# Line_Follower.net
KiCad netlist of a schematic drawn in EAGLE
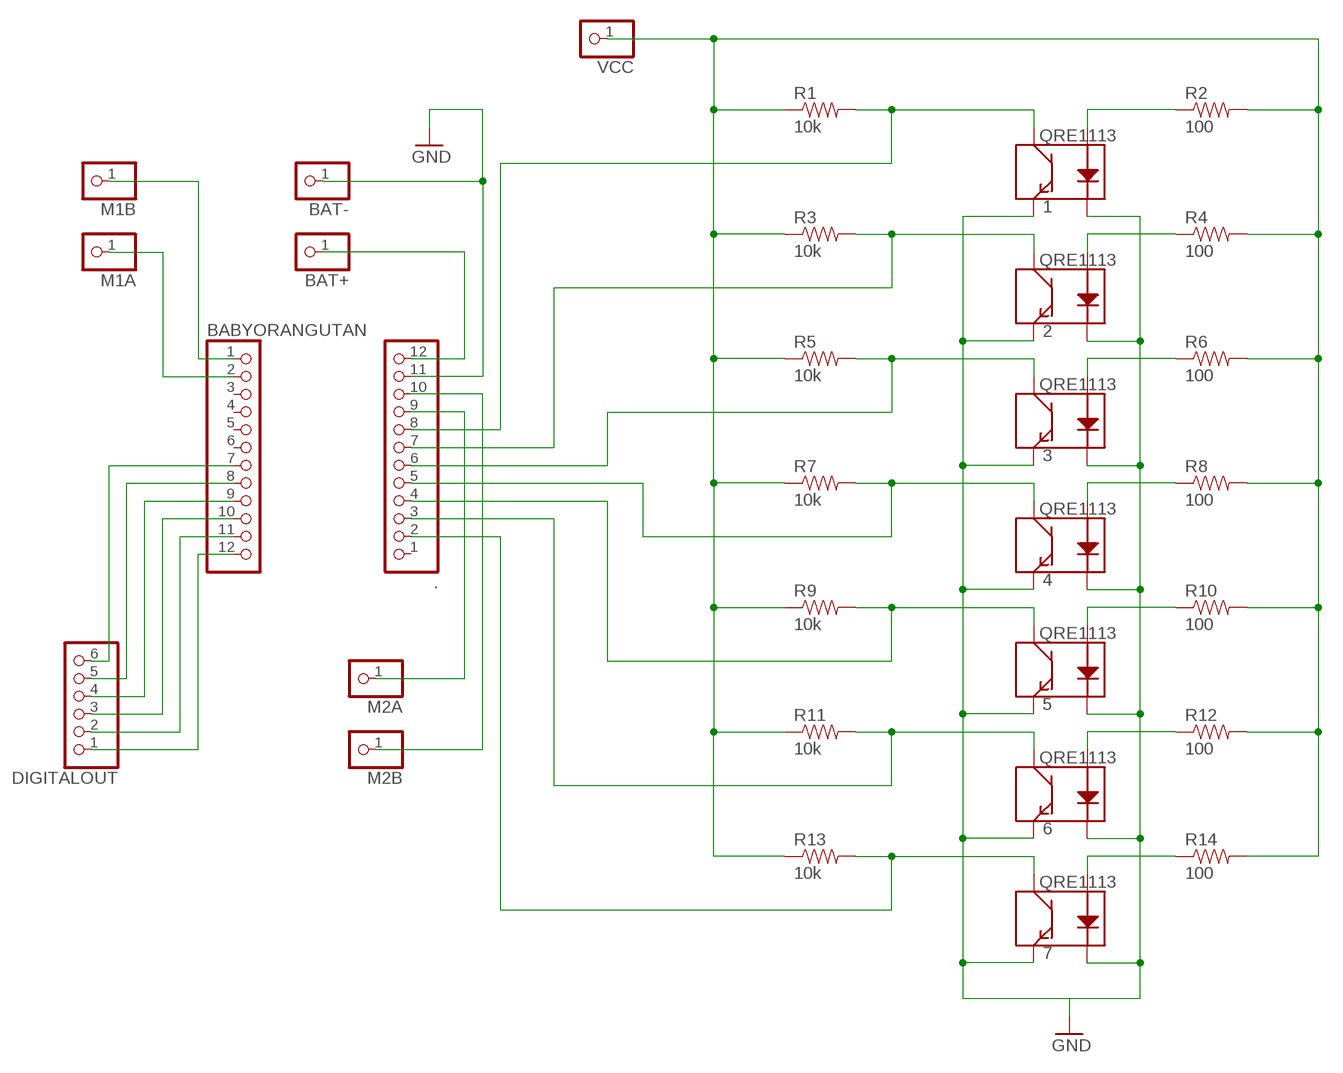
[diagram p0: schematic, sheet 1]

(export (version "E")
  (design (tool "Eeschema 10.0.6"))
  (components
    (comp (ref ".")
      (value "PINHD-1X12")
      (footprint "eagle-import:1X12")
      (libsource (lib "eagle-import") (part "PINHD-1X12"))
    )
    (comp (ref "1")
      (value "QRE1113")
      (footprint "eagle-import:QRE1113")
      (libsource (lib "eagle-import") (part "QRE1113"))
    )
    (comp (ref "2")
      (value "QRE1113")
      (footprint "eagle-import:QRE1113")
      (libsource (lib "eagle-import") (part "QRE1113"))
    )
    (comp (ref "3")
      (value "QRE1113")
      (footprint "eagle-import:QRE1113")
      (libsource (lib "eagle-import") (part "QRE1113"))
    )
    (comp (ref "4")
      (value "QRE1113")
      (footprint "eagle-import:QRE1113")
      (libsource (lib "eagle-import") (part "QRE1113"))
    )
    (comp (ref "5")
      (value "QRE1113")
      (footprint "eagle-import:QRE1113")
      (libsource (lib "eagle-import") (part "QRE1113"))
    )
    (comp (ref "6")
      (value "QRE1113")
      (footprint "eagle-import:QRE1113")
      (libsource (lib "eagle-import") (part "QRE1113"))
    )
    (comp (ref "7")
      (value "QRE1113")
      (footprint "eagle-import:QRE1113")
      (libsource (lib "eagle-import") (part "QRE1113"))
    )
    (comp (ref "BABYORANGUTAN")
      (value "PINHD-1X12")
      (footprint "eagle-import:1X12")
      (libsource (lib "eagle-import") (part "PINHD-1X12"))
    )
    (comp (ref "BAT+")
      (value "PINHD-1X1")
      (footprint "eagle-import:1X01")
      (libsource (lib "eagle-import") (part "PINHD-1X1"))
    )
    (comp (ref "BAT-")
      (value "PINHD-1X1")
      (footprint "eagle-import:1X01")
      (libsource (lib "eagle-import") (part "PINHD-1X1"))
    )
    (comp (ref "DIGITALOUT")
      (value "PINHD-1X6")
      (footprint "eagle-import:1X06")
      (libsource (lib "eagle-import") (part "PINHD-1X6"))
    )
    (comp (ref "M1A")
      (value "PINHD-1X1")
      (footprint "eagle-import:1X01")
      (libsource (lib "eagle-import") (part "PINHD-1X1"))
    )
    (comp (ref "M1B")
      (value "PINHD-1X1")
      (footprint "eagle-import:1X01")
      (libsource (lib "eagle-import") (part "PINHD-1X1"))
    )
    (comp (ref "M2A")
      (value "PINHD-1X1")
      (footprint "eagle-import:1X01")
      (libsource (lib "eagle-import") (part "PINHD-1X1"))
    )
    (comp (ref "M2B")
      (value "PINHD-1X1")
      (footprint "eagle-import:1X01")
      (libsource (lib "eagle-import") (part "PINHD-1X1"))
    )
    (comp (ref "R1")
      (value "10k")
      (footprint "eagle-import:0603-RES")
      (libsource (lib "eagle-import") (part "RESISTOR0603-RES"))
    )
    (comp (ref "R2")
      (value "100")
      (footprint "eagle-import:0805")
      (libsource (lib "eagle-import") (part "RESISTOR0805-RES"))
    )
    (comp (ref "R3")
      (value "10k")
      (footprint "eagle-import:0603-RES")
      (libsource (lib "eagle-import") (part "RESISTOR0603-RES"))
    )
    (comp (ref "R4")
      (value "100")
      (footprint "eagle-import:0805")
      (libsource (lib "eagle-import") (part "RESISTOR0805-RES"))
    )
    (comp (ref "R5")
      (value "10k")
      (footprint "eagle-import:0603-RES")
      (libsource (lib "eagle-import") (part "RESISTOR0603-RES"))
    )
    (comp (ref "R6")
      (value "100")
      (footprint "eagle-import:0805")
      (libsource (lib "eagle-import") (part "RESISTOR0805-RES"))
    )
    (comp (ref "R7")
      (value "10k")
      (footprint "eagle-import:0603-RES")
      (libsource (lib "eagle-import") (part "RESISTOR0603-RES"))
    )
    (comp (ref "R8")
      (value "100")
      (footprint "eagle-import:0805")
      (libsource (lib "eagle-import") (part "RESISTOR0805-RES"))
    )
    (comp (ref "R9")
      (value "10k")
      (footprint "eagle-import:0603-RES")
      (libsource (lib "eagle-import") (part "RESISTOR0603-RES"))
    )
    (comp (ref "R10")
      (value "100")
      (footprint "eagle-import:0805")
      (libsource (lib "eagle-import") (part "RESISTOR0805-RES"))
    )
    (comp (ref "R11")
      (value "10k")
      (footprint "eagle-import:0603-RES")
      (libsource (lib "eagle-import") (part "RESISTOR0603-RES"))
    )
    (comp (ref "R12")
      (value "100")
      (footprint "eagle-import:0805")
      (libsource (lib "eagle-import") (part "RESISTOR0805-RES"))
    )
    (comp (ref "R13")
      (value "10k")
      (footprint "eagle-import:0603-RES")
      (libsource (lib "eagle-import") (part "RESISTOR0603-RES"))
    )
    (comp (ref "R14")
      (value "100")
      (footprint "eagle-import:0805")
      (libsource (lib "eagle-import") (part "RESISTOR0805-RES"))
    )
    (comp (ref "VCC")
      (value "PINHD-1X1")
      (footprint "eagle-import:1X01")
      (libsource (lib "eagle-import") (part "PINHD-1X1"))
    )
  )
  (nets
    (net (code "1") (name "GND") (class "Default")
      (node (ref ".") (pin "11") (pinfunction "11_11") (pintype "passive"))
      (node (ref "1") (pin "2") (pinfunction "K_2") (pintype "bidirectional"))
      (node (ref "1") (pin "4") (pinfunction "E_4") (pintype "bidirectional"))
      (node (ref "2") (pin "2") (pinfunction "K_2") (pintype "bidirectional"))
      (node (ref "2") (pin "4") (pinfunction "E_4") (pintype "bidirectional"))
      (node (ref "3") (pin "2") (pinfunction "K_2") (pintype "bidirectional"))
      (node (ref "3") (pin "4") (pinfunction "E_4") (pintype "bidirectional"))
      (node (ref "4") (pin "2") (pinfunction "K_2") (pintype "bidirectional"))
      (node (ref "4") (pin "4") (pinfunction "E_4") (pintype "bidirectional"))
      (node (ref "5") (pin "2") (pinfunction "K_2") (pintype "bidirectional"))
      (node (ref "5") (pin "4") (pinfunction "E_4") (pintype "bidirectional"))
      (node (ref "6") (pin "2") (pinfunction "K_2") (pintype "bidirectional"))
      (node (ref "6") (pin "4") (pinfunction "E_4") (pintype "bidirectional"))
      (node (ref "7") (pin "2") (pinfunction "K_2") (pintype "bidirectional"))
      (node (ref "7") (pin "4") (pinfunction "E_4") (pintype "bidirectional"))
      (node (ref "BAT-") (pin "1") (pinfunction "1_1") (pintype "passive"))
    )
    (net (code "2") (name "Net-(.-Pad9)") (class "Default")
      (node (ref ".") (pin "9") (pinfunction "9_9") (pintype "passive"))
      (node (ref "M2A") (pin "1") (pinfunction "1_1") (pintype "passive"))
    )
    (net (code "3") (name "Net-(.-Pad10)") (class "Default")
      (node (ref ".") (pin "10") (pinfunction "10_10") (pintype "passive"))
      (node (ref "M2B") (pin "1") (pinfunction "1_1") (pintype "passive"))
    )
    (net (code "4") (name "Net-(.-Pad12)") (class "Default")
      (node (ref ".") (pin "12") (pinfunction "12_12") (pintype "passive"))
      (node (ref "BAT+") (pin "1") (pinfunction "1_1") (pintype "passive"))
    )
    (net (code "5") (name "Net-(1-A)") (class "Default")
      (node (ref "1") (pin "1") (pinfunction "A_1") (pintype "bidirectional"))
      (node (ref "R2") (pin "1") (pinfunction "1_1") (pintype "passive"))
    )
    (net (code "6") (name "Net-(1-C)") (class "Default")
      (node (ref ".") (pin "8") (pinfunction "8_8") (pintype "passive"))
      (node (ref "1") (pin "3") (pinfunction "C_3") (pintype "bidirectional"))
      (node (ref "R1") (pin "2") (pinfunction "2_2") (pintype "passive"))
    )
    (net (code "7") (name "Net-(2-A)") (class "Default")
      (node (ref "2") (pin "1") (pinfunction "A_1") (pintype "bidirectional"))
      (node (ref "R4") (pin "1") (pinfunction "1_1") (pintype "passive"))
    )
    (net (code "8") (name "Net-(2-C)") (class "Default")
      (node (ref ".") (pin "7") (pinfunction "7_7") (pintype "passive"))
      (node (ref "2") (pin "3") (pinfunction "C_3") (pintype "bidirectional"))
      (node (ref "R3") (pin "2") (pinfunction "2_2") (pintype "passive"))
    )
    (net (code "9") (name "Net-(3-A)") (class "Default")
      (node (ref "3") (pin "1") (pinfunction "A_1") (pintype "bidirectional"))
      (node (ref "R6") (pin "1") (pinfunction "1_1") (pintype "passive"))
    )
    (net (code "10") (name "Net-(3-C)") (class "Default")
      (node (ref ".") (pin "6") (pinfunction "6_6") (pintype "passive"))
      (node (ref "3") (pin "3") (pinfunction "C_3") (pintype "bidirectional"))
      (node (ref "R5") (pin "2") (pinfunction "2_2") (pintype "passive"))
    )
    (net (code "11") (name "Net-(4-A)") (class "Default")
      (node (ref "4") (pin "1") (pinfunction "A_1") (pintype "bidirectional"))
      (node (ref "R8") (pin "1") (pinfunction "1_1") (pintype "passive"))
    )
    (net (code "12") (name "Net-(4-C)") (class "Default")
      (node (ref ".") (pin "5") (pinfunction "5_5") (pintype "passive"))
      (node (ref "4") (pin "3") (pinfunction "C_3") (pintype "bidirectional"))
      (node (ref "R7") (pin "2") (pinfunction "2_2") (pintype "passive"))
    )
    (net (code "13") (name "Net-(5-A)") (class "Default")
      (node (ref "5") (pin "1") (pinfunction "A_1") (pintype "bidirectional"))
      (node (ref "R10") (pin "1") (pinfunction "1_1") (pintype "passive"))
    )
    (net (code "14") (name "Net-(5-C)") (class "Default")
      (node (ref ".") (pin "4") (pinfunction "4_4") (pintype "passive"))
      (node (ref "5") (pin "3") (pinfunction "C_3") (pintype "bidirectional"))
      (node (ref "R9") (pin "2") (pinfunction "2_2") (pintype "passive"))
    )
    (net (code "15") (name "Net-(6-A)") (class "Default")
      (node (ref "6") (pin "1") (pinfunction "A_1") (pintype "bidirectional"))
      (node (ref "R12") (pin "1") (pinfunction "1_1") (pintype "passive"))
    )
    (net (code "16") (name "Net-(6-C)") (class "Default")
      (node (ref ".") (pin "3") (pinfunction "3_3") (pintype "passive"))
      (node (ref "6") (pin "3") (pinfunction "C_3") (pintype "bidirectional"))
      (node (ref "R11") (pin "2") (pinfunction "2_2") (pintype "passive"))
    )
    (net (code "17") (name "Net-(7-A)") (class "Default")
      (node (ref "7") (pin "1") (pinfunction "A_1") (pintype "bidirectional"))
      (node (ref "R14") (pin "1") (pinfunction "1_1") (pintype "passive"))
    )
    (net (code "18") (name "Net-(7-C)") (class "Default")
      (node (ref ".") (pin "2") (pinfunction "2_2") (pintype "passive"))
      (node (ref "7") (pin "3") (pinfunction "C_3") (pintype "bidirectional"))
      (node (ref "R13") (pin "2") (pinfunction "2_2") (pintype "passive"))
    )
    (net (code "19") (name "Net-(BABYORANGUTAN-Pad1)") (class "Default")
      (node (ref "BABYORANGUTAN") (pin "1") (pinfunction "1_1") (pintype "passive"))
      (node (ref "M1B") (pin "1") (pinfunction "1_1") (pintype "passive"))
    )
    (net (code "20") (name "Net-(BABYORANGUTAN-Pad2)") (class "Default")
      (node (ref "BABYORANGUTAN") (pin "2") (pinfunction "2_2") (pintype "passive"))
      (node (ref "M1A") (pin "1") (pinfunction "1_1") (pintype "passive"))
    )
    (net (code "21") (name "Net-(BABYORANGUTAN-Pad7)") (class "Default")
      (node (ref "BABYORANGUTAN") (pin "7") (pinfunction "7_7") (pintype "passive"))
      (node (ref "DIGITALOUT") (pin "6") (pinfunction "6_6") (pintype "passive"))
    )
    (net (code "22") (name "Net-(BABYORANGUTAN-Pad8)") (class "Default")
      (node (ref "BABYORANGUTAN") (pin "8") (pinfunction "8_8") (pintype "passive"))
      (node (ref "DIGITALOUT") (pin "5") (pinfunction "5_5") (pintype "passive"))
    )
    (net (code "23") (name "Net-(BABYORANGUTAN-Pad9)") (class "Default")
      (node (ref "BABYORANGUTAN") (pin "9") (pinfunction "9_9") (pintype "passive"))
      (node (ref "DIGITALOUT") (pin "4") (pinfunction "4_4") (pintype "passive"))
    )
    (net (code "24") (name "Net-(BABYORANGUTAN-Pad10)") (class "Default")
      (node (ref "BABYORANGUTAN") (pin "10") (pinfunction "10_10") (pintype "passive"))
      (node (ref "DIGITALOUT") (pin "3") (pinfunction "3_3") (pintype "passive"))
    )
    (net (code "25") (name "Net-(BABYORANGUTAN-Pad11)") (class "Default")
      (node (ref "BABYORANGUTAN") (pin "11") (pinfunction "11_11") (pintype "passive"))
      (node (ref "DIGITALOUT") (pin "2") (pinfunction "2_2") (pintype "passive"))
    )
    (net (code "26") (name "Net-(BABYORANGUTAN-Pad12)") (class "Default")
      (node (ref "BABYORANGUTAN") (pin "12") (pinfunction "12_12") (pintype "passive"))
      (node (ref "DIGITALOUT") (pin "1") (pinfunction "1_1") (pintype "passive"))
    )
    (net (code "27") (name "Net-(R1-Pad1)") (class "Default")
      (node (ref "R1") (pin "1") (pinfunction "1_1") (pintype "passive"))
      (node (ref "R10") (pin "2") (pinfunction "2_2") (pintype "passive"))
      (node (ref "R11") (pin "1") (pinfunction "1_1") (pintype "passive"))
      (node (ref "R12") (pin "2") (pinfunction "2_2") (pintype "passive"))
      (node (ref "R13") (pin "1") (pinfunction "1_1") (pintype "passive"))
      (node (ref "R14") (pin "2") (pinfunction "2_2") (pintype "passive"))
      (node (ref "R2") (pin "2") (pinfunction "2_2") (pintype "passive"))
      (node (ref "R3") (pin "1") (pinfunction "1_1") (pintype "passive"))
      (node (ref "R4") (pin "2") (pinfunction "2_2") (pintype "passive"))
      (node (ref "R5") (pin "1") (pinfunction "1_1") (pintype "passive"))
      (node (ref "R6") (pin "2") (pinfunction "2_2") (pintype "passive"))
      (node (ref "R7") (pin "1") (pinfunction "1_1") (pintype "passive"))
      (node (ref "R8") (pin "2") (pinfunction "2_2") (pintype "passive"))
      (node (ref "R9") (pin "1") (pinfunction "1_1") (pintype "passive"))
      (node (ref "VCC") (pin "1") (pinfunction "1_1") (pintype "passive"))
    )
    (net (code "28") (name "unconnected-(.-Pad1)") (class "Default")
      (node (ref ".") (pin "1") (pinfunction "1_1") (pintype "passive"))
    )
    (net (code "29") (name "unconnected-(BABYORANGUTAN-Pad3)") (class "Default")
      (node (ref "BABYORANGUTAN") (pin "3") (pinfunction "3_3") (pintype "passive"))
    )
    (net (code "30") (name "unconnected-(BABYORANGUTAN-Pad4)") (class "Default")
      (node (ref "BABYORANGUTAN") (pin "4") (pinfunction "4_4") (pintype "passive"))
    )
    (net (code "31") (name "unconnected-(BABYORANGUTAN-Pad5)") (class "Default")
      (node (ref "BABYORANGUTAN") (pin "5") (pinfunction "5_5") (pintype "passive"))
    )
    (net (code "32") (name "unconnected-(BABYORANGUTAN-Pad6)") (class "Default")
      (node (ref "BABYORANGUTAN") (pin "6") (pinfunction "6_6") (pintype "passive"))
    )
  )
)
